# Ganhuangguan.net
KiCad netlist of a schematic drawn in Altium Designer
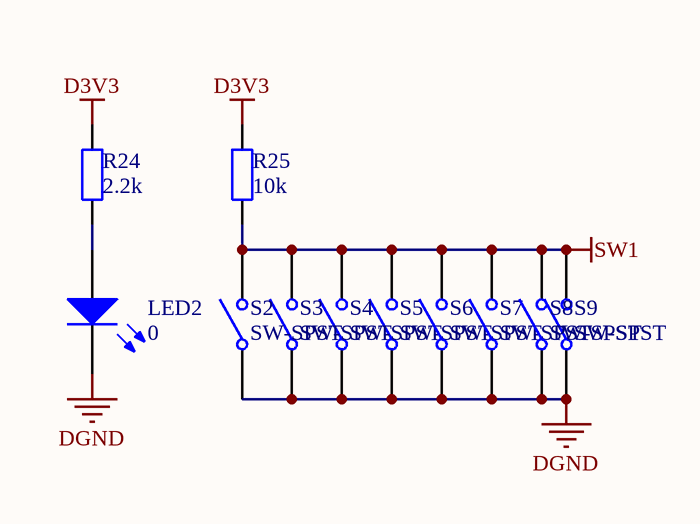
[diagram p0: Ganhuangguan.SchDoc]

(export (version "E")
  (design (tool "Eeschema 10.0.6"))
  (components
    (comp (ref "LED2")
      (value "0")
      (footprint "0603C")
      (description "Typical RED, GREEN, YELLOW, AMBER GaAs LED")
      (fields (field (name "PUBLISHER") "Altium Limited"))
      (libsource (lib "Schlib1") (part "LED2"))
    )
    (comp (ref "R24")
      (value "2.2k")
      (footprint "0603R")
      (description "Resistor")
      (fields (field (name "Comment") "Res2") (field (name "PUBLISHER") "Altium Limited"))
      (libsource (lib "Schlib1") (part "Res2"))
    )
    (comp (ref "R25")
      (value "10k")
      (footprint "0603C")
      (description "Resistor")
      (fields (field (name "Comment") "Res2") (field (name "PUBLISHER") "Altium Limited"))
      (libsource (lib "Schlib1") (part "Res2"))
    )
    (comp (ref "S2")
      (value "SW-SPST")
      (footprint "SW_REED")
      (description "Single-Pole, Single-Throw Switch")
      (fields (field (name "PUBLISHER") "Altium Limited"))
      (libsource (lib "Miscellaneous Devices") (part "SW-SPST"))
    )
    (comp (ref "S3")
      (value "SW-SPST")
      (footprint "SW_REED")
      (description "Single-Pole, Single-Throw Switch")
      (fields (field (name "PUBLISHER") "Altium Limited"))
      (libsource (lib "Miscellaneous Devices") (part "SW-SPST"))
    )
    (comp (ref "S4")
      (value "SW-SPST")
      (footprint "SW_REED")
      (description "Single-Pole, Single-Throw Switch")
      (fields (field (name "PUBLISHER") "Altium Limited"))
      (libsource (lib "Miscellaneous Devices") (part "SW-SPST"))
    )
    (comp (ref "S5")
      (value "SW-SPST")
      (footprint "SW_REED")
      (description "Single-Pole, Single-Throw Switch")
      (fields (field (name "PUBLISHER") "Altium Limited"))
      (libsource (lib "Miscellaneous Devices") (part "SW-SPST"))
    )
    (comp (ref "S6")
      (value "SW-SPST")
      (footprint "SW_REED")
      (description "Single-Pole, Single-Throw Switch")
      (fields (field (name "PUBLISHER") "Altium Limited"))
      (libsource (lib "Miscellaneous Devices") (part "SW-SPST"))
    )
    (comp (ref "S7")
      (value "SW-SPST")
      (footprint "SW_REED")
      (description "Single-Pole, Single-Throw Switch")
      (fields (field (name "PUBLISHER") "Altium Limited"))
      (libsource (lib "Miscellaneous Devices") (part "SW-SPST"))
    )
    (comp (ref "S8")
      (value "SW-SPST")
      (footprint "SW_REED")
      (description "Single-Pole, Single-Throw Switch")
      (fields (field (name "PUBLISHER") "Altium Limited"))
      (libsource (lib "Miscellaneous Devices") (part "SW-SPST"))
    )
    (comp (ref "S9")
      (value "SW-SPST")
      (footprint "SW_REED")
      (description "Single-Pole, Single-Throw Switch")
      (fields (field (name "PUBLISHER") "Altium Limited"))
      (libsource (lib "Miscellaneous Devices") (part "SW-SPST"))
    )
  )
  (nets
    (net (code "1") (name "D3V3") (class "Default")
      (node (ref "R24") (pin "2") (pinfunction "2_2") (pintype "passive"))
      (node (ref "R25") (pin "2") (pinfunction "2_2") (pintype "passive"))
    )
    (net (code "2") (name "DGND") (class "Default")
      (node (ref "LED2") (pin "2") (pinfunction "K_2") (pintype "passive"))
      (node (ref "S2") (pin "1") (pinfunction "COMMON_1") (pintype "passive"))
      (node (ref "S3") (pin "1") (pinfunction "COMMON_1") (pintype "passive"))
      (node (ref "S4") (pin "1") (pinfunction "COMMON_1") (pintype "passive"))
      (node (ref "S5") (pin "1") (pinfunction "COMMON_1") (pintype "passive"))
      (node (ref "S6") (pin "1") (pinfunction "COMMON_1") (pintype "passive"))
      (node (ref "S7") (pin "1") (pinfunction "COMMON_1") (pintype "passive"))
      (node (ref "S8") (pin "1") (pinfunction "COMMON_1") (pintype "passive"))
      (node (ref "S9") (pin "1") (pinfunction "COMMON_1") (pintype "passive"))
    )
    (net (code "3") (name "Net-(LED2-A)") (class "Default")
      (node (ref "LED2") (pin "1") (pinfunction "A_1") (pintype "passive"))
      (node (ref "R24") (pin "1") (pinfunction "1_1") (pintype "passive"))
    )
    (net (code "4") (name "SW1") (class "Default")
      (node (ref "R25") (pin "1") (pinfunction "1_1") (pintype "passive"))
      (node (ref "S2") (pin "2") (pinfunction "NO_2") (pintype "passive"))
      (node (ref "S3") (pin "2") (pinfunction "NO_2") (pintype "passive"))
      (node (ref "S4") (pin "2") (pinfunction "NO_2") (pintype "passive"))
      (node (ref "S5") (pin "2") (pinfunction "NO_2") (pintype "passive"))
      (node (ref "S6") (pin "2") (pinfunction "NO_2") (pintype "passive"))
      (node (ref "S7") (pin "2") (pinfunction "NO_2") (pintype "passive"))
      (node (ref "S8") (pin "2") (pinfunction "NO_2") (pintype "passive"))
      (node (ref "S9") (pin "2") (pinfunction "NO_2") (pintype "passive"))
    )
  )
)
